# power.net
KiCad netlist of a schematic drawn in Altium Designer
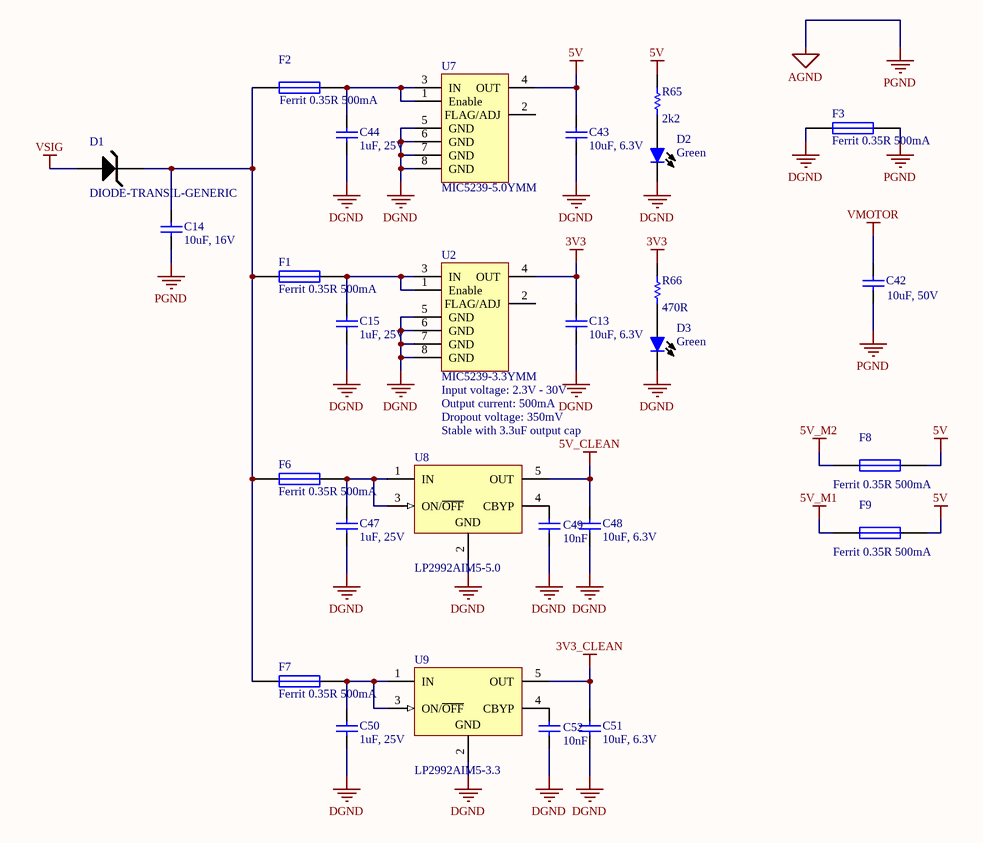
[diagram p0: power.SchDoc]

(export (version "E")
  (design (tool "Eeschema 10.0.6"))
  (components
    (comp (ref "C13")
      (value "10uF, 6.3V")
      (footprint "CAPC1608L")
      (description "Capacitor (Semiconductor SIM Model)")
      (fields (field (name "PUBLISHER") "Altium Limited"))
      (libsource (lib "Miscellaneous Devices") (part "Cap Semi"))
    )
    (comp (ref "C14")
      (value "10uF, 16V")
      (footprint "CAPC2512L")
      (description "Capacitor (Semiconductor SIM Model)")
      (fields (field (name "PUBLISHER") "Altium Limited"))
      (libsource (lib "Miscellaneous Devices") (part "Cap Semi"))
    )
    (comp (ref "C15")
      (value "1uF, 25V")
      (footprint "CAPC2512L")
      (description "Capacitor (Semiconductor SIM Model)")
      (fields (field (name "PUBLISHER") "Altium Limited"))
      (libsource (lib "Miscellaneous Devices") (part "Cap Semi"))
    )
    (comp (ref "C42")
      (value "10uF, 50V")
      (footprint "CAPC3216L")
      (description "Capacitor (Semiconductor SIM Model)")
      (fields (field (name "VOLTAGE") "50V") (field (name "PUBLISHER") "Altium Limited"))
      (libsource (lib "Miscellaneous Devices") (part "Cap Semi"))
    )
    (comp (ref "C43")
      (value "10uF, 6.3V")
      (footprint "CAPC1608L")
      (description "Capacitor (Semiconductor SIM Model)")
      (fields (field (name "PUBLISHER") "Altium Limited"))
      (libsource (lib "Miscellaneous Devices") (part "Cap Semi"))
    )
    (comp (ref "C44")
      (value "1uF, 25V")
      (footprint "CAPC1608L")
      (description "Capacitor (Semiconductor SIM Model)")
      (fields (field (name "PUBLISHER") "Altium Limited"))
      (libsource (lib "Miscellaneous Devices") (part "Cap Semi"))
    )
    (comp (ref "C47")
      (value "1uF, 25V")
      (footprint "CAPC1608L")
      (description "Capacitor (Semiconductor SIM Model)")
      (fields (field (name "PUBLISHER") "Altium Limited"))
      (libsource (lib "Miscellaneous Devices") (part "Cap Semi"))
    )
    (comp (ref "C48")
      (value "10uF, 6.3V")
      (footprint "CAPC1608L")
      (description "Capacitor (Semiconductor SIM Model)")
      (fields (field (name "PUBLISHER") "Altium Limited"))
      (libsource (lib "Miscellaneous Devices") (part "Cap Semi"))
    )
    (comp (ref "C49")
      (value "10nF")
      (footprint "CAPC1608L")
      (description "Capacitor (Semiconductor SIM Model)")
      (fields (field (name "PUBLISHER") "Altium Limited"))
      (libsource (lib "Miscellaneous Devices") (part "Cap Semi"))
    )
    (comp (ref "C50")
      (value "1uF, 25V")
      (footprint "CAPC1608L")
      (description "Capacitor (Semiconductor SIM Model)")
      (fields (field (name "PUBLISHER") "Altium Limited"))
      (libsource (lib "Miscellaneous Devices") (part "Cap Semi"))
    )
    (comp (ref "C51")
      (value "10uF, 6.3V")
      (footprint "CAPC1608L")
      (description "Capacitor (Semiconductor SIM Model)")
      (fields (field (name "PUBLISHER") "Altium Limited"))
      (libsource (lib "Miscellaneous Devices") (part "Cap Semi"))
    )
    (comp (ref "C52")
      (value "10nF")
      (footprint "CAPC1608L")
      (description "Capacitor (Semiconductor SIM Model)")
      (fields (field (name "PUBLISHER") "Altium Limited"))
      (libsource (lib "Miscellaneous Devices") (part "Cap Semi"))
    )
    (comp (ref "D1")
      (value "DIODE-TRANSIL-GENERIC")
      (footprint "DIODE-SMB")
      (description "GENERIC TRANSIL")
      (libsource (lib "vh_Altium Library") (part "DIODE-TRANSIL-GENERIC"))
    )
    (comp (ref "D2")
      (value "LED Green")
      (footprint "CD1608-0603")
      (description "LED")
      (fields (field (name "COLOR") "Green"))
      (libsource (lib "Roombots") (part "LED"))
    )
    (comp (ref "D3")
      (value "LED Green")
      (footprint "CD1608-0603")
      (description "LED")
      (fields (field (name "COLOR") "Green"))
      (libsource (lib "Roombots") (part "LED"))
    )
    (comp (ref "F1")
      (value "Ferrit 0.35R 500mA")
      (footprint "RESC1608L")
      (description "Ferrit Bead")
      (fields (field (name "PUBLISHER") "Altium Limited"))
      (libsource (lib "Miscellaneous Devices") (part "Fuse 1"))
    )
    (comp (ref "F2")
      (value "Ferrit 0.35R 500mA")
      (footprint "RESC1608L")
      (description "Ferrit Bead")
      (fields (field (name "PUBLISHER") "Altium Limited"))
      (libsource (lib "Miscellaneous Devices") (part "Fuse 1"))
    )
    (comp (ref "F3")
      (value "Ferrit 0.35R 500mA")
      (footprint "RESC1608L")
      (description "Ferrit Bead")
      (fields (field (name "PUBLISHER") "Altium Limited"))
      (libsource (lib "Miscellaneous Devices") (part "Fuse 1"))
    )
    (comp (ref "F6")
      (value "Ferrit 0.35R 500mA")
      (footprint "RESC1608L")
      (description "Ferrit Bead")
      (fields (field (name "PUBLISHER") "Altium Limited"))
      (libsource (lib "Miscellaneous Devices") (part "Fuse 1"))
    )
    (comp (ref "F7")
      (value "Ferrit 0.35R 500mA")
      (footprint "RESC1608L")
      (description "Ferrit Bead")
      (fields (field (name "PUBLISHER") "Altium Limited"))
      (libsource (lib "Miscellaneous Devices") (part "Fuse 1"))
    )
    (comp (ref "F8")
      (value "Ferrit 0.35R 500mA")
      (footprint "RESC1608L")
      (description "Ferrit Bead")
      (fields (field (name "PUBLISHER") "Altium Limited"))
      (libsource (lib "Miscellaneous Devices") (part "Fuse 1"))
    )
    (comp (ref "F9")
      (value "Ferrit 0.35R 500mA")
      (footprint "RESC1608L")
      (description "Ferrit Bead")
      (fields (field (name "PUBLISHER") "Altium Limited"))
      (libsource (lib "Miscellaneous Devices") (part "Fuse 1"))
    )
    (comp (ref "R65")
      (value "2k2")
      (footprint "RESC1608L")
      (description "Semiconductor Resistor")
      (fields (field (name "PUBLISHER") "Altium Limited"))
      (libsource (lib "Miscellaneous Devices") (part "Res Semi"))
    )
    (comp (ref "R66")
      (value "470R")
      (footprint "RESC1608L")
      (description "Semiconductor Resistor")
      (fields (field (name "PUBLISHER") "Altium Limited"))
      (libsource (lib "Miscellaneous Devices") (part "Res Semi"))
    )
    (comp (ref "U2")
      (value "MIC5239-3.3YMM")
      (footprint "MSOP-8")
      (description "LDO, 500mA, Vin:2.3V-30V")
      (libsource (lib "Roombots") (part "MIC5239"))
    )
    (comp (ref "U7")
      (value "MIC5239-5.0YMM")
      (footprint "MSOP-8")
      (description "LDO, 500mA, Vin:2.3V-30V")
      (libsource (lib "Roombots") (part "MIC5239"))
    )
    (comp (ref "U8")
      (value "LP2992AIM5-5.0")
      (footprint "MF05A_N")
      (description "Micropower 250 mA Low-Noise Ultra Low-Dropout Regulator in SOT-23 and LLP Packages")
      (fields
        (field (name "MANUFACTURER") "National Semiconductor")
        (field (name "DIGIKEYPARTNUMBER") "LP2992AIM5-5.0CT-ND")
        (field (name "PUBLISHER") "Altium Limited")
      )
      (libsource (lib "NSC LDO") (part "LP2992AIM5-5.0"))
    )
    (comp (ref "U9")
      (value "LP2992AIM5-3.3")
      (footprint "MF05A_N")
      (description "Micropower 250 mA Low-Noise Ultra Low-Dropout Regulator in SOT-23 and LLP Packages")
      (fields
        (field (name "PARTNUMBER") "LP2992AIM5-5.0")
        (field (name "MANUFACTURER") "National Semiconductor")
        (field (name "PUBLISHER") "Altium Limited")
      )
      (libsource (lib "NSC LDO") (part "LP2992AIM5-5.0"))
    )
  )
  (nets
    (net (code "1") (name "3V3") (class "Default")
      (node (ref "C13") (pin "2") (pinfunction "2_2") (pintype "passive"))
      (node (ref "R66") (pin "2") (pinfunction "2_2") (pintype "passive"))
      (node (ref "U2") (pin "4") (pinfunction "OUT_4") (pintype "power_in"))
    )
    (net (code "2") (name "3V3_CLEAN") (class "Default")
      (node (ref "C51") (pin "2") (pinfunction "2_2") (pintype "passive"))
      (node (ref "U9") (pin "5") (pinfunction "OUT_5") (pintype "power_in"))
    )
    (net (code "3") (name "5V") (class "Default")
      (node (ref "C43") (pin "2") (pinfunction "2_2") (pintype "passive"))
      (node (ref "F8") (pin "2") (pinfunction "2_2") (pintype "passive"))
      (node (ref "F9") (pin "2") (pinfunction "2_2") (pintype "passive"))
      (node (ref "R65") (pin "2") (pinfunction "2_2") (pintype "passive"))
      (node (ref "U7") (pin "4") (pinfunction "OUT_4") (pintype "power_in"))
    )
    (net (code "4") (name "5V_CLEAN") (class "Default")
      (node (ref "C48") (pin "2") (pinfunction "2_2") (pintype "passive"))
      (node (ref "U8") (pin "5") (pinfunction "OUT_5") (pintype "power_in"))
    )
    (net (code "5") (name "5V_M1") (class "Default")
      (node (ref "F9") (pin "1") (pinfunction "1_1") (pintype "passive"))
    )
    (net (code "6") (name "5V_M2") (class "Default")
      (node (ref "F8") (pin "1") (pinfunction "1_1") (pintype "passive"))
    )
    (net (code "7") (name "AGND") (class "Default")
      (node (ref "C14") (pin "1") (pinfunction "1_1") (pintype "passive"))
      (node (ref "C42") (pin "1") (pinfunction "1_1") (pintype "passive"))
      (node (ref "F3") (pin "2") (pinfunction "2_2") (pintype "passive"))
    )
    (net (code "8") (name "DGND") (class "Default")
      (node (ref "C13") (pin "1") (pinfunction "1_1") (pintype "passive"))
      (node (ref "C15") (pin "1") (pinfunction "1_1") (pintype "passive"))
      (node (ref "C43") (pin "1") (pinfunction "1_1") (pintype "passive"))
      (node (ref "C44") (pin "1") (pinfunction "1_1") (pintype "passive"))
      (node (ref "C47") (pin "1") (pinfunction "1_1") (pintype "passive"))
      (node (ref "C48") (pin "1") (pinfunction "1_1") (pintype "passive"))
      (node (ref "C49") (pin "1") (pinfunction "1_1") (pintype "passive"))
      (node (ref "C50") (pin "1") (pinfunction "1_1") (pintype "passive"))
      (node (ref "C51") (pin "1") (pinfunction "1_1") (pintype "passive"))
      (node (ref "C52") (pin "1") (pinfunction "1_1") (pintype "passive"))
      (node (ref "D2") (pin "2") (pinfunction "C_2") (pintype "passive"))
      (node (ref "D3") (pin "2") (pinfunction "C_2") (pintype "passive"))
      (node (ref "F3") (pin "1") (pinfunction "1_1") (pintype "passive"))
      (node (ref "U2") (pin "5") (pinfunction "GND_5") (pintype "power_in"))
      (node (ref "U2") (pin "6") (pinfunction "GND_6") (pintype "power_in"))
      (node (ref "U2") (pin "7") (pinfunction "GND_7") (pintype "power_in"))
      (node (ref "U2") (pin "8") (pinfunction "GND_8") (pintype "power_in"))
      (node (ref "U7") (pin "5") (pinfunction "GND_5") (pintype "power_in"))
      (node (ref "U7") (pin "6") (pinfunction "GND_6") (pintype "power_in"))
      (node (ref "U7") (pin "7") (pinfunction "GND_7") (pintype "power_in"))
      (node (ref "U7") (pin "8") (pinfunction "GND_8") (pintype "power_in"))
      (node (ref "U8") (pin "2") (pinfunction "GND_2") (pintype "power_in"))
      (node (ref "U9") (pin "2") (pinfunction "GND_2") (pintype "power_in"))
    )
    (net (code "9") (name "Net-(C14-Pad2)") (class "Default")
      (node (ref "C14") (pin "2") (pinfunction "2_2") (pintype "passive"))
      (node (ref "D1") (pin "K") (pinfunction "K_K") (pintype "passive"))
      (node (ref "F1") (pin "1") (pinfunction "1_1") (pintype "passive"))
      (node (ref "F2") (pin "1") (pinfunction "1_1") (pintype "passive"))
      (node (ref "F6") (pin "1") (pinfunction "1_1") (pintype "passive"))
      (node (ref "F7") (pin "1") (pinfunction "1_1") (pintype "passive"))
    )
    (net (code "10") (name "Net-(D2-A)") (class "Default")
      (node (ref "D2") (pin "1") (pinfunction "A_1") (pintype "passive"))
      (node (ref "R65") (pin "1") (pinfunction "1_1") (pintype "passive"))
    )
    (net (code "11") (name "Net-(D3-A)") (class "Default")
      (node (ref "D3") (pin "1") (pinfunction "A_1") (pintype "passive"))
      (node (ref "R66") (pin "1") (pinfunction "1_1") (pintype "passive"))
    )
    (net (code "12") (name "Net-(U2-Enable)") (class "Default")
      (node (ref "C15") (pin "2") (pinfunction "2_2") (pintype "passive"))
      (node (ref "F1") (pin "2") (pinfunction "2_2") (pintype "passive"))
      (node (ref "U2") (pin "1") (pinfunction "Enable_1") (pintype "passive"))
      (node (ref "U2") (pin "3") (pinfunction "IN_3") (pintype "power_in"))
    )
    (net (code "13") (name "Net-(U7-Enable)") (class "Default")
      (node (ref "C44") (pin "2") (pinfunction "2_2") (pintype "passive"))
      (node (ref "F2") (pin "2") (pinfunction "2_2") (pintype "passive"))
      (node (ref "U7") (pin "1") (pinfunction "Enable_1") (pintype "passive"))
      (node (ref "U7") (pin "3") (pinfunction "IN_3") (pintype "power_in"))
    )
    (net (code "14") (name "Net-(U8-CBYP)") (class "Default")
      (node (ref "C49") (pin "2") (pinfunction "2_2") (pintype "passive"))
      (node (ref "U8") (pin "4") (pinfunction "CBYP_4") (pintype "passive"))
    )
    (net (code "15") (name "Net-(U8-IN)") (class "Default")
      (node (ref "C47") (pin "2") (pinfunction "2_2") (pintype "passive"))
      (node (ref "F6") (pin "2") (pinfunction "2_2") (pintype "passive"))
      (node (ref "U8") (pin "1") (pinfunction "IN_1") (pintype "power_in"))
      (node (ref "U8") (pin "3") (pinfunction "ON/~{OFF}_3") (pintype "input"))
    )
    (net (code "16") (name "Net-(U9-CBYP)") (class "Default")
      (node (ref "C52") (pin "2") (pinfunction "2_2") (pintype "passive"))
      (node (ref "U9") (pin "4") (pinfunction "CBYP_4") (pintype "passive"))
    )
    (net (code "17") (name "Net-(U9-IN)") (class "Default")
      (node (ref "C50") (pin "2") (pinfunction "2_2") (pintype "passive"))
      (node (ref "F7") (pin "2") (pinfunction "2_2") (pintype "passive"))
      (node (ref "U9") (pin "1") (pinfunction "IN_1") (pintype "power_in"))
      (node (ref "U9") (pin "3") (pinfunction "ON/~{OFF}_3") (pintype "input"))
    )
    (net (code "18") (name "VMOTOR") (class "Default")
      (node (ref "C42") (pin "2") (pinfunction "2_2") (pintype "passive"))
    )
    (net (code "19") (name "VSIG") (class "Default")
      (node (ref "D1") (pin "A") (pinfunction "A_A") (pintype "passive"))
    )
    (net (code "20") (name "unconnected-(U2-FLAG{slash}ADJ-Pad2)") (class "Default")
      (node (ref "U2") (pin "2") (pinfunction "FLAG/ADJ_2") (pintype "passive"))
    )
    (net (code "21") (name "unconnected-(U7-FLAG{slash}ADJ-Pad2)") (class "Default")
      (node (ref "U7") (pin "2") (pinfunction "FLAG/ADJ_2") (pintype "passive"))
    )
  )
)
